# RX-FM-Super-Regenerative-2.net
KiCad netlist of a schematic drawn in EAGLE
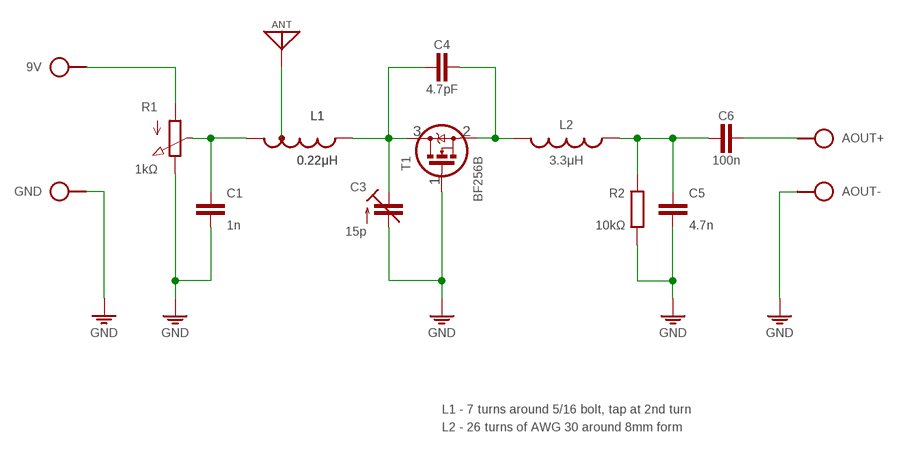
[diagram p0: schematic, sheet 1]

(export (version "E")
  (design (tool "Eeschema 10.0.6"))
  (components
    (comp (ref "9V")
      (value "SPAD")
      (footprint "eagle-import:SPAD")
      (libsource (lib "eagle-import") (part "SPAD"))
    )
    (comp (ref "ANT")
      (value "ANT")
      (footprint "eagle-import:SPAD")
      (libsource (lib "eagle-import") (part "ANT"))
    )
    (comp (ref "AOUT+")
      (value "SPAD")
      (footprint "eagle-import:SPAD")
      (libsource (lib "eagle-import") (part "SPAD"))
    )
    (comp (ref "AOUT-")
      (value "SPAD")
      (footprint "eagle-import:SPAD")
      (libsource (lib "eagle-import") (part "SPAD"))
    )
    (comp (ref "C1")
      (value "1n")
      (footprint "eagle-import:C050-025X060")
      (libsource (lib "eagle-import") (part "C025-025X060"))
    )
    (comp (ref "C3")
      (value "15p")
      (footprint "eagle-import:TRIM-2222-808")
      (libsource (lib "eagle-import") (part "C-TR-PH201272222-808-2PINB"))
    )
    (comp (ref "C4")
      (value "4.7pF")
      (footprint "eagle-import:C025-020X036")
      (libsource (lib "eagle-import") (part "C025-020X036"))
    )
    (comp (ref "C5")
      (value "4.7n")
      (footprint "eagle-import:C050-020X044")
      (libsource (lib "eagle-import") (part "C050-020X044"))
    )
    (comp (ref "C6")
      (value "100n")
      (footprint "eagle-import:C050-020X044")
      (libsource (lib "eagle-import") (part "C050-020X044"))
    )
    (comp (ref "GND")
      (value "SPAD")
      (footprint "eagle-import:SPAD")
      (libsource (lib "eagle-import") (part "SPAD"))
    )
    (comp (ref "L1")
      (value "0.22μH")
      (footprint "eagle-import:L-08_12-X-TAP1")
      (libsource (lib "eagle-import") (part "L-TAP1L-08/12-X-TAP1"))
    )
    (comp (ref "L2")
      (value "3.3μH")
      (footprint "eagle-import:L-BODY")
      (libsource (lib "eagle-import") (part "L-BODY"))
    )
    (comp (ref "R1")
      (value "1kΩ")
      (footprint "eagle-import:POT")
      (libsource (lib "eagle-import") (part "POT"))
    )
    (comp (ref "R2")
      (value "10kΩ")
      (footprint "eagle-import:0204_10")
      (libsource (lib "eagle-import") (part "R0204/10"))
    )
    (comp (ref "T1")
      (value "BF256B")
      (footprint "eagle-import:TO92")
      (libsource (lib "eagle-import") (part "BF256B"))
    )
  )
  (nets
    (net (code "1") (name "GND") (class "Default")
      (node (ref "AOUT-") (pin "1") (pinfunction "P$1_1") (pintype "bidirectional"))
      (node (ref "C1") (pin "2") (pinfunction "2_2") (pintype "passive"))
      (node (ref "C3") (pin "2") (pinfunction "A_2") (pintype "passive"))
      (node (ref "C5") (pin "2") (pinfunction "2_2") (pintype "passive"))
      (node (ref "GND") (pin "1") (pinfunction "P$1_1") (pintype "bidirectional"))
      (node (ref "R1") (pin "3") (pinfunction "E_3") (pintype "passive"))
      (node (ref "R2") (pin "1") (pinfunction "1_1") (pintype "passive"))
      (node (ref "T1") (pin "1") (pinfunction "G_1") (pintype "passive"))
    )
    (net (code "2") (name "Net-(9V-P$1)") (class "Default")
      (node (ref "9V") (pin "1") (pinfunction "P$1_1") (pintype "bidirectional"))
      (node (ref "R1") (pin "1") (pinfunction "A_1") (pintype "passive"))
    )
    (net (code "3") (name "Net-(AOUT+-P$1)") (class "Default")
      (node (ref "AOUT+") (pin "1") (pinfunction "P$1_1") (pintype "bidirectional"))
      (node (ref "C6") (pin "2") (pinfunction "2_2") (pintype "passive"))
    )
    (net (code "4") (name "Net-(C3-E)") (class "Default")
      (node (ref "C3") (pin "3") (pinfunction "E_3") (pintype "passive"))
      (node (ref "C4") (pin "1") (pinfunction "1_1") (pintype "passive"))
      (node (ref "L1") (pin "2") (pinfunction "2_2") (pintype "passive"))
      (node (ref "T1") (pin "3") (pinfunction "D_3") (pintype "passive"))
    )
    (net (code "5") (name "Net-(L1-T)") (class "Default")
      (node (ref "ANT") (pin "1") (pinfunction "1_1") (pintype "output"))
      (node (ref "L1") (pin "3") (pinfunction "T_3") (pintype "passive"))
    )
    (net (code "6") (name "Net-(L2-1)") (class "Default")
      (node (ref "C5") (pin "1") (pinfunction "1_1") (pintype "passive"))
      (node (ref "C6") (pin "1") (pinfunction "1_1") (pintype "passive"))
      (node (ref "L2") (pin "2") (pinfunction "1_2") (pintype "passive"))
      (node (ref "R2") (pin "2") (pinfunction "2_2") (pintype "passive"))
    )
    (net (code "7") (name "Net-(L2-2)") (class "Default")
      (node (ref "C4") (pin "2") (pinfunction "2_2") (pintype "passive"))
      (node (ref "L2") (pin "3") (pinfunction "2_3") (pintype "passive"))
      (node (ref "T1") (pin "2") (pinfunction "S_2") (pintype "passive"))
    )
    (net (code "8") (name "Net-(R1-S)") (class "Default")
      (node (ref "C1") (pin "1") (pinfunction "1_1") (pintype "passive"))
      (node (ref "L1") (pin "1") (pinfunction "1_1") (pintype "passive"))
      (node (ref "R1") (pin "2") (pinfunction "S_2") (pintype "passive"))
    )
  )
)
